# OneShot_Relais_Timer.net
KiCad netlist of a schematic drawn in EAGLE
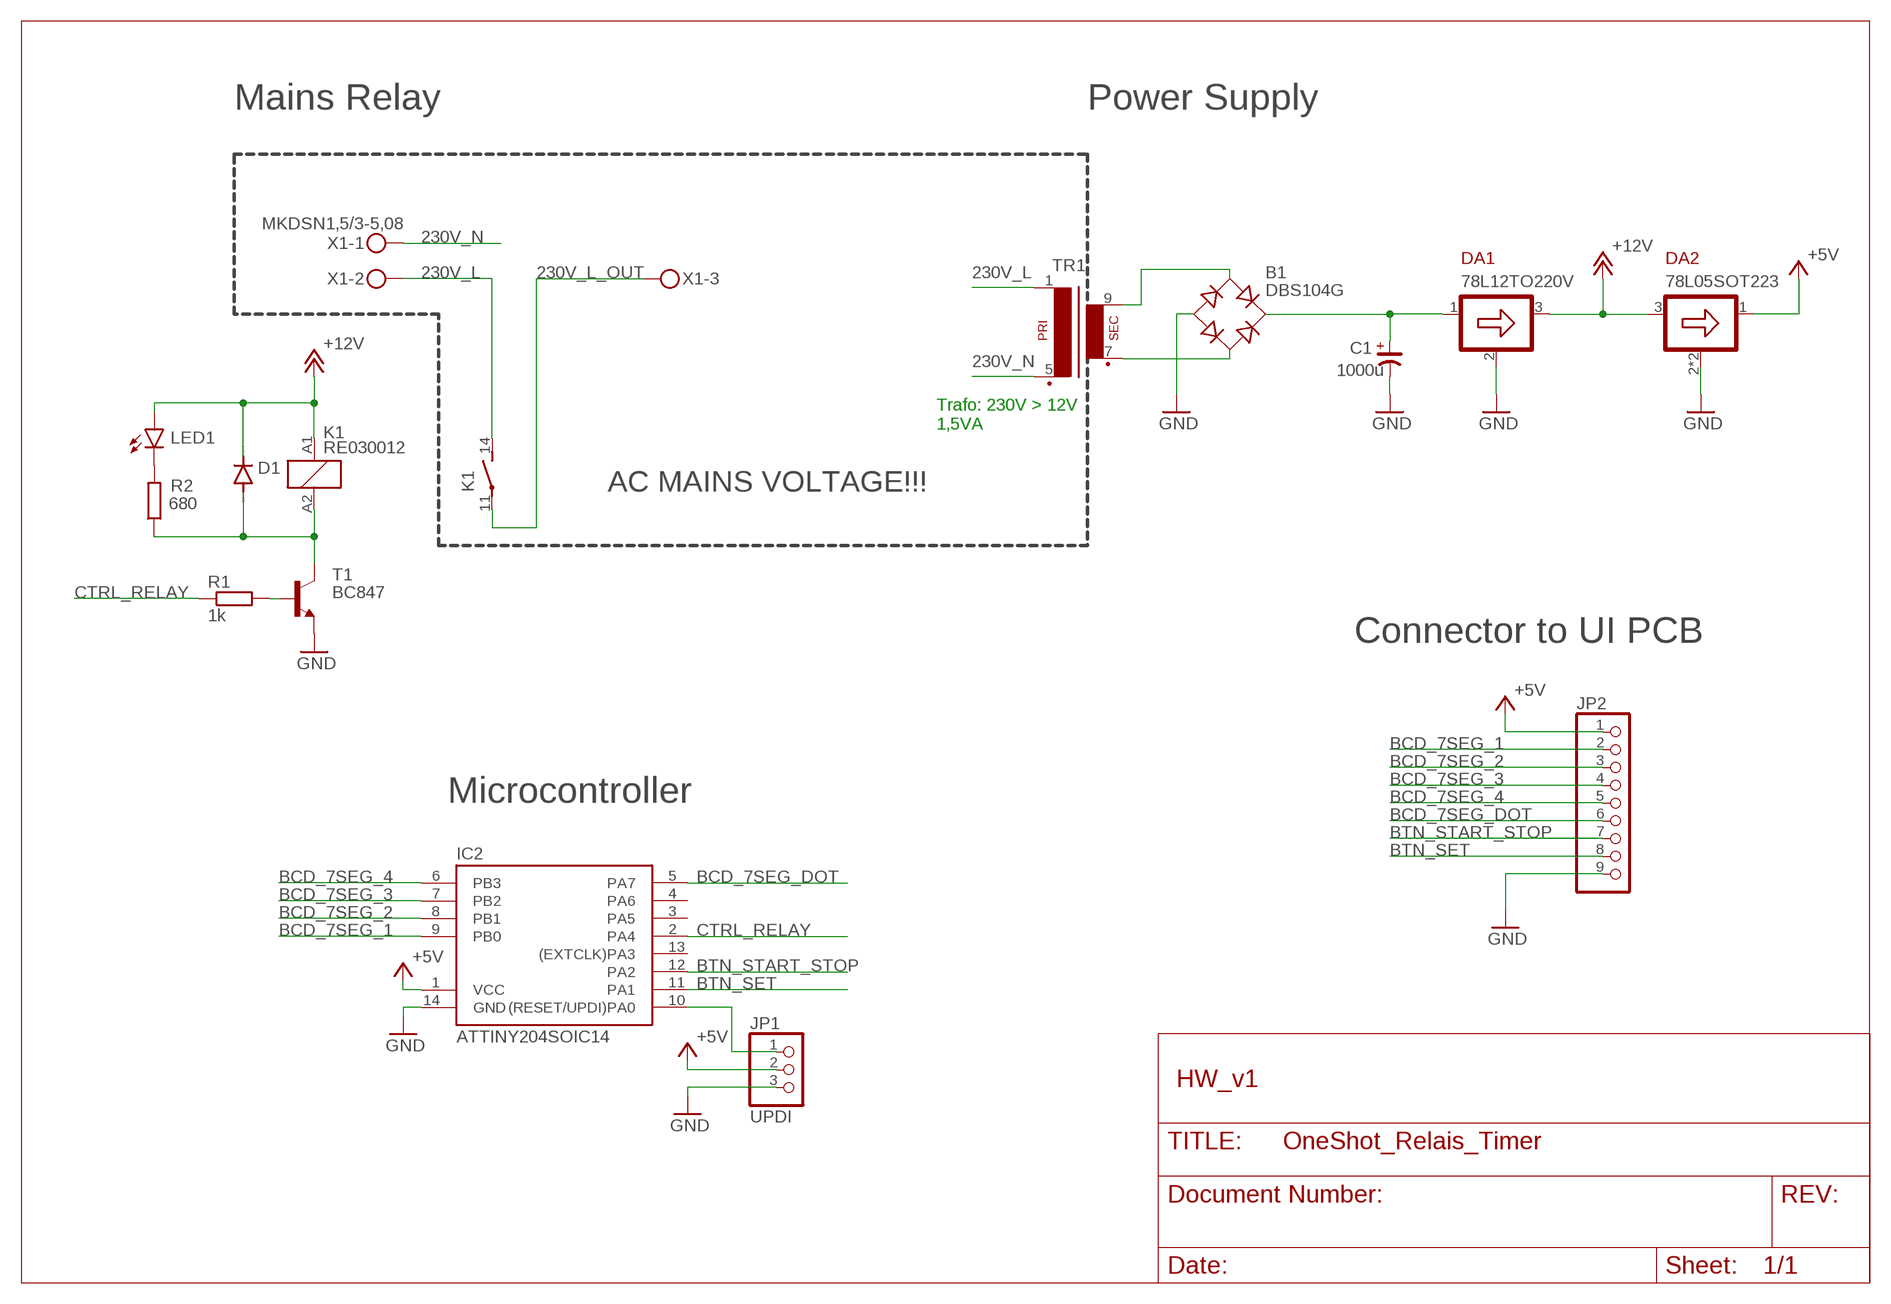
[diagram p0: schematic, sheet 1]

(export (version "E")
  (design (tool "Eeschema 10.0.6"))
  (components
    (comp (ref "B1")
      (value "DBS104G")
      (footprint "eagle-import:DBS")
      (libsource (lib "eagle-import") (part "DB?GS104"))
    )
    (comp (ref "C1")
      (value "1000u")
      (footprint "eagle-import:CSV-G")
      (libsource (lib "eagle-import") (part "CP_"))
    )
    (comp (ref "D1")
      (value "DIODE-SOD80C")
      (footprint "eagle-import:SOD80C")
      (libsource (lib "eagle-import") (part "DIODE-SOD80C"))
    )
    (comp (ref "DA1")
      (value "78L12TO220V")
      (footprint "eagle-import:TO220V")
      (libsource (lib "eagle-import") (part "78L12TO220V"))
    )
    (comp (ref "DA2")
      (value "78L05SOT223")
      (footprint "eagle-import:SOT223")
      (libsource (lib "eagle-import") (part "78L05SOT223"))
    )
    (comp (ref "IC2")
      (value "ATTINY204SOIC14")
      (footprint "eagle-import:SOIC127P600X175-14N")
      (libsource (lib "eagle-import") (part "ATTINY204SOIC14"))
    )
    (comp (ref "JP1")
      (value "UPDI")
      (footprint "eagle-import:1X03")
      (libsource (lib "eagle-import") (part "PINHD-1X3"))
    )
    (comp (ref "JP2")
      (value "PINHD-1X9")
      (footprint "eagle-import:1X09")
      (libsource (lib "eagle-import") (part "PINHD-1X9"))
    )
    (comp (ref "K1")
      (value "RE030012")
      (footprint "eagle-import:RE-SCHRACK")
      (fields (field (name "MF") "TYCO ELECTRONICS"))
      (libsource (lib "eagle-import") (part "RE030012"))
    )
    (comp (ref "LED1")
      (value "LED5MM")
      (footprint "eagle-import:LED5MM")
      (libsource (lib "eagle-import") (part "LED5MM"))
    )
    (comp (ref "R1")
      (value "1k")
      (footprint "eagle-import:R0805")
      (libsource (lib "eagle-import") (part "R-EU_R0805"))
    )
    (comp (ref "R2")
      (value "680")
      (footprint "eagle-import:R0805")
      (libsource (lib "eagle-import") (part "R-EU_R0805"))
    )
    (comp (ref "T1")
      (value "BC847")
      (footprint "eagle-import:SOT23")
      (libsource (lib "eagle-import") (part "BC847"))
    )
    (comp (ref "TR1")
      (value "EI30-12.5")
      (footprint "eagle-import:EI30-1")
      (libsource (lib "eagle-import") (part "EI30-12.5"))
    )
    (comp (ref "X1")
      (value "MKDSN1,5/3-5,08")
      (footprint "eagle-import:MKDSN1,5_3-5,08")
      (libsource (lib "eagle-import") (part "MKDSN1,5/3-5,08"))
    )
  )
  (nets
    (net (code "1") (name "+5V") (class "Default")
      (node (ref "DA2") (pin "1") (pinfunction "OUT_1") (pintype "power_in"))
      (node (ref "IC2") (pin "1") (pinfunction "VCC_1") (pintype "power_in"))
      (node (ref "JP1") (pin "2") (pinfunction "2_2") (pintype "passive"))
      (node (ref "JP2") (pin "1") (pinfunction "1_1") (pintype "passive"))
    )
    (net (code "2") (name "+12V") (class "Default")
      (node (ref "D1") (pin "C") (pinfunction "C_C") (pintype "passive"))
      (node (ref "DA1") (pin "3") (pinfunction "OUT_3") (pintype "power_in"))
      (node (ref "DA2") (pin "3") (pinfunction "IN_3") (pintype "power_in"))
      (node (ref "K1") (pin "A1") (pinfunction "1_A1") (pintype "passive"))
      (node (ref "LED1") (pin "A") (pinfunction "A_A") (pintype "passive"))
    )
    (net (code "3") (name "/230V_L") (class "Default")
      (node (ref "K1") (pin "14") (pinfunction "S_14") (pintype "passive"))
      (node (ref "TR1") (pin "1") (pinfunction "P1_1") (pintype "passive"))
      (node (ref "X1") (pin "2") (pinfunction "KL_2") (pintype "passive"))
    )
    (net (code "4") (name "/230V_L_OUT") (class "Default")
      (node (ref "K1") (pin "11") (pinfunction "P_11") (pintype "passive"))
      (node (ref "X1") (pin "3") (pinfunction "KL_3") (pintype "passive"))
    )
    (net (code "5") (name "/230V_N") (class "Default")
      (node (ref "TR1") (pin "5") (pinfunction "P2_5") (pintype "passive"))
      (node (ref "X1") (pin "1") (pinfunction "KL_1") (pintype "passive"))
    )
    (net (code "6") (name "/BCD_7SEG_1") (class "Default")
      (node (ref "IC2") (pin "9") (pinfunction "PB0_9") (pintype "bidirectional"))
      (node (ref "JP2") (pin "2") (pinfunction "2_2") (pintype "passive"))
    )
    (net (code "7") (name "/BCD_7SEG_2") (class "Default")
      (node (ref "IC2") (pin "8") (pinfunction "PB1_8") (pintype "bidirectional"))
      (node (ref "JP2") (pin "3") (pinfunction "3_3") (pintype "passive"))
    )
    (net (code "8") (name "/BCD_7SEG_3") (class "Default")
      (node (ref "IC2") (pin "7") (pinfunction "PB2_7") (pintype "bidirectional"))
      (node (ref "JP2") (pin "4") (pinfunction "4_4") (pintype "passive"))
    )
    (net (code "9") (name "/BCD_7SEG_4") (class "Default")
      (node (ref "IC2") (pin "6") (pinfunction "PB3_6") (pintype "bidirectional"))
      (node (ref "JP2") (pin "5") (pinfunction "5_5") (pintype "passive"))
    )
    (net (code "10") (name "/BCD_7SEG_DOT") (class "Default")
      (node (ref "IC2") (pin "5") (pinfunction "PA7_5") (pintype "bidirectional"))
      (node (ref "JP2") (pin "6") (pinfunction "6_6") (pintype "passive"))
    )
    (net (code "11") (name "/BTN_SET") (class "Default")
      (node (ref "IC2") (pin "11") (pinfunction "PA1_11") (pintype "bidirectional"))
      (node (ref "JP2") (pin "8") (pinfunction "8_8") (pintype "passive"))
    )
    (net (code "12") (name "/BTN_START_STOP") (class "Default")
      (node (ref "IC2") (pin "12") (pinfunction "PA2_12") (pintype "bidirectional"))
      (node (ref "JP2") (pin "7") (pinfunction "7_7") (pintype "passive"))
    )
    (net (code "13") (name "/CTRL_RELAY") (class "Default")
      (node (ref "IC2") (pin "2") (pinfunction "PA4_2") (pintype "bidirectional"))
      (node (ref "R1") (pin "1") (pinfunction "1_1") (pintype "passive"))
    )
    (net (code "14") (name "GND") (class "Default")
      (node (ref "B1") (pin "-") (pinfunction "-_-") (pintype "passive"))
      (node (ref "C1") (pin "-") (pinfunction "-_-") (pintype "passive"))
      (node (ref "DA1") (pin "2") (pinfunction "GND_2") (pintype "power_in"))
      (node (ref "DA2") (pin "2") (pinfunction "GND_2") (pintype "power_in"))
      (node (ref "DA2") (pin "4") (pinfunction "GND_4") (pintype "power_in"))
      (node (ref "IC2") (pin "14") (pinfunction "GND_14") (pintype "power_in"))
      (node (ref "JP1") (pin "3") (pinfunction "3_3") (pintype "passive"))
      (node (ref "JP2") (pin "9") (pinfunction "9_9") (pintype "passive"))
      (node (ref "T1") (pin "2") (pinfunction "E_2") (pintype "passive"))
    )
    (net (code "15") (name "Net-(DA1-IN)") (class "Default")
      (node (ref "B1") (pin "+") (pinfunction "+_+") (pintype "passive"))
      (node (ref "C1") (pin "+") (pinfunction "+_+") (pintype "passive"))
      (node (ref "DA1") (pin "1") (pinfunction "IN_1") (pintype "power_in"))
    )
    (net (code "16") (name "Net-(IC2-(RESET{slash}UPDI)PA0)") (class "Default")
      (node (ref "IC2") (pin "10") (pinfunction "(RESET/UPDI)PA0_10") (pintype "bidirectional"))
      (node (ref "JP1") (pin "1") (pinfunction "1_1") (pintype "passive"))
    )
    (net (code "17") (name "Net-(K1A-2)") (class "Default")
      (node (ref "D1") (pin "A") (pinfunction "A_A") (pintype "passive"))
      (node (ref "K1") (pin "A2") (pinfunction "2_A2") (pintype "passive"))
      (node (ref "R2") (pin "1") (pinfunction "1_1") (pintype "passive"))
      (node (ref "T1") (pin "3") (pinfunction "C_3") (pintype "passive"))
    )
    (net (code "18") (name "Net-(LED1-C)") (class "Default")
      (node (ref "LED1") (pin "K") (pinfunction "C_K") (pintype "passive"))
      (node (ref "R2") (pin "2") (pinfunction "2_2") (pintype "passive"))
    )
    (net (code "19") (name "Net-(T1-B)") (class "Default")
      (node (ref "R1") (pin "2") (pinfunction "2_2") (pintype "passive"))
      (node (ref "T1") (pin "1") (pinfunction "B_1") (pintype "passive"))
    )
    (net (code "20") (name "Net-(TR1-S3)") (class "Default")
      (node (ref "B1") (pin "AC2") (pinfunction "AC2_AC2") (pintype "passive"))
      (node (ref "TR1") (pin "7") (pinfunction "S3_7") (pintype "passive"))
    )
    (net (code "21") (name "Net-(TR1-S4)") (class "Default")
      (node (ref "B1") (pin "AC1") (pinfunction "AC1_AC1") (pintype "passive"))
      (node (ref "TR1") (pin "9") (pinfunction "S4_9") (pintype "passive"))
    )
    (net (code "22") (name "unconnected-(IC2-(EXTCLK)PA3-Pad13)") (class "Default")
      (node (ref "IC2") (pin "13") (pinfunction "(EXTCLK)PA3_13") (pintype "bidirectional"))
    )
    (net (code "23") (name "unconnected-(IC2-PA5-Pad3)") (class "Default")
      (node (ref "IC2") (pin "3") (pinfunction "PA5_3") (pintype "bidirectional"))
    )
    (net (code "24") (name "unconnected-(IC2-PA6-Pad4)") (class "Default")
      (node (ref "IC2") (pin "4") (pinfunction "PA6_4") (pintype "bidirectional"))
    )
  )
)
